# ser-handsh_01.net
KiCad netlist of a schematic drawn in EAGLE
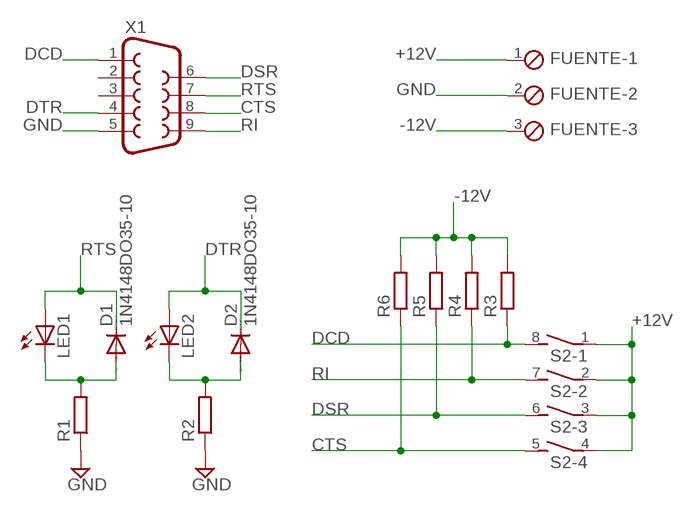
[diagram p0: schematic, sheet 1]

(export (version "E")
  (design (tool "Eeschema 10.0.6"))
  (components
    (comp (ref "D1")
      (value "1N4148DO35-10")
      (footprint "eagle-import:DO35-10")
      (libsource (lib "eagle-import") (part "1N4148DO35-10"))
    )
    (comp (ref "D2")
      (value "1N4148DO35-10")
      (footprint "eagle-import:DO35-10")
      (libsource (lib "eagle-import") (part "1N4148DO35-10"))
    )
    (comp (ref "FUENTE")
      (value "MPT3")
      (footprint "eagle-import:3POL254")
      (fields (field (name "MPN") "444"))
      (libsource (lib "eagle-import") (part "MPT3"))
    )
    (comp (ref "LED1")
      (value "LED5MM")
      (footprint "eagle-import:LED5MM")
      (libsource (lib "eagle-import") (part "LED5MM"))
    )
    (comp (ref "LED2")
      (value "LED5MM")
      (footprint "eagle-import:LED5MM")
      (libsource (lib "eagle-import") (part "LED5MM"))
    )
    (comp (ref "R1")
      (value "R-EU_0207/10")
      (footprint "eagle-import:0207_10")
      (libsource (lib "eagle-import") (part "R-EU_0207/10"))
    )
    (comp (ref "R2")
      (value "R-EU_0207/10")
      (footprint "eagle-import:0207_10")
      (libsource (lib "eagle-import") (part "R-EU_0207/10"))
    )
    (comp (ref "R3")
      (value "R-EU_0207/10")
      (footprint "eagle-import:0207_10")
      (libsource (lib "eagle-import") (part "R-EU_0207/10"))
    )
    (comp (ref "R4")
      (value "R-EU_0207/10")
      (footprint "eagle-import:0207_10")
      (libsource (lib "eagle-import") (part "R-EU_0207/10"))
    )
    (comp (ref "R5")
      (value "R-EU_0207/10")
      (footprint "eagle-import:0207_10")
      (libsource (lib "eagle-import") (part "R-EU_0207/10"))
    )
    (comp (ref "R6")
      (value "R-EU_0207/10")
      (footprint "eagle-import:0207_10")
      (libsource (lib "eagle-import") (part "R-EU_0207/10"))
    )
    (comp (ref "S2")
      (value "DIP04S")
      (footprint "eagle-import:DIP04S")
      (libsource (lib "eagle-import") (part "DIP04S"))
    )
    (comp (ref "X1")
      (value "F09HP")
      (footprint "eagle-import:F09HP")
      (libsource (lib "eagle-import") (part "F09HP"))
    )
  )
  (nets
    (net (code "1") (name "/+12V") (class "Default")
      (node (ref "FUENTE") (pin "1") (pinfunction "1_1") (pintype "passive"))
      (node (ref "S2") (pin "1") (pinfunction "1_1") (pintype "passive"))
      (node (ref "S2") (pin "2") (pinfunction "1_2") (pintype "passive"))
      (node (ref "S2") (pin "3") (pinfunction "1_3") (pintype "passive"))
      (node (ref "S2") (pin "4") (pinfunction "1_4") (pintype "passive"))
    )
    (net (code "2") (name "/-12V") (class "Default")
      (node (ref "FUENTE") (pin "3") (pinfunction "1_3") (pintype "passive"))
      (node (ref "R3") (pin "2") (pinfunction "2_2") (pintype "passive"))
      (node (ref "R4") (pin "2") (pinfunction "2_2") (pintype "passive"))
      (node (ref "R5") (pin "2") (pinfunction "2_2") (pintype "passive"))
      (node (ref "R6") (pin "2") (pinfunction "2_2") (pintype "passive"))
    )
    (net (code "3") (name "/CTS") (class "Default")
      (node (ref "R6") (pin "1") (pinfunction "1_1") (pintype "passive"))
      (node (ref "S2") (pin "5") (pinfunction "2_5") (pintype "passive"))
      (node (ref "X1") (pin "8") (pinfunction "8_8") (pintype "passive"))
    )
    (net (code "4") (name "/DCD") (class "Default")
      (node (ref "R3") (pin "1") (pinfunction "1_1") (pintype "passive"))
      (node (ref "S2") (pin "8") (pinfunction "2_8") (pintype "passive"))
      (node (ref "X1") (pin "1") (pinfunction "1_1") (pintype "passive"))
    )
    (net (code "5") (name "/DSR") (class "Default")
      (node (ref "R5") (pin "1") (pinfunction "1_1") (pintype "passive"))
      (node (ref "S2") (pin "6") (pinfunction "2_6") (pintype "passive"))
      (node (ref "X1") (pin "6") (pinfunction "6_6") (pintype "passive"))
    )
    (net (code "6") (name "/DTR") (class "Default")
      (node (ref "D2") (pin "C") (pinfunction "C_C") (pintype "passive"))
      (node (ref "LED2") (pin "A") (pinfunction "A_A") (pintype "passive"))
      (node (ref "X1") (pin "4") (pinfunction "4_4") (pintype "passive"))
    )
    (net (code "7") (name "/RI") (class "Default")
      (node (ref "R4") (pin "1") (pinfunction "1_1") (pintype "passive"))
      (node (ref "S2") (pin "7") (pinfunction "2_7") (pintype "passive"))
      (node (ref "X1") (pin "9") (pinfunction "9_9") (pintype "passive"))
    )
    (net (code "8") (name "/RTS") (class "Default")
      (node (ref "D1") (pin "C") (pinfunction "C_C") (pintype "passive"))
      (node (ref "LED1") (pin "A") (pinfunction "A_A") (pintype "passive"))
      (node (ref "X1") (pin "7") (pinfunction "7_7") (pintype "passive"))
    )
    (net (code "9") (name "GND") (class "Default")
      (node (ref "FUENTE") (pin "2") (pinfunction "1_2") (pintype "passive"))
      (node (ref "R1") (pin "1") (pinfunction "1_1") (pintype "passive"))
      (node (ref "R2") (pin "1") (pinfunction "1_1") (pintype "passive"))
      (node (ref "X1") (pin "5") (pinfunction "5_5") (pintype "passive"))
    )
    (net (code "10") (name "Net-(LED1-C)") (class "Default")
      (node (ref "D1") (pin "A") (pinfunction "A_A") (pintype "passive"))
      (node (ref "LED1") (pin "K") (pinfunction "C_K") (pintype "passive"))
      (node (ref "R1") (pin "2") (pinfunction "2_2") (pintype "passive"))
    )
    (net (code "11") (name "Net-(LED2-C)") (class "Default")
      (node (ref "D2") (pin "A") (pinfunction "A_A") (pintype "passive"))
      (node (ref "LED2") (pin "K") (pinfunction "C_K") (pintype "passive"))
      (node (ref "R2") (pin "2") (pinfunction "2_2") (pintype "passive"))
    )
    (net (code "12") (name "unconnected-(X1-Pad2)") (class "Default")
      (node (ref "X1") (pin "2") (pinfunction "2_2") (pintype "passive"))
    )
    (net (code "13") (name "unconnected-(X1-Pad3)") (class "Default")
      (node (ref "X1") (pin "3") (pinfunction "3_3") (pintype "passive"))
    )
  )
)
